# pwr.net
KiCad netlist of a schematic drawn in Altium Designer
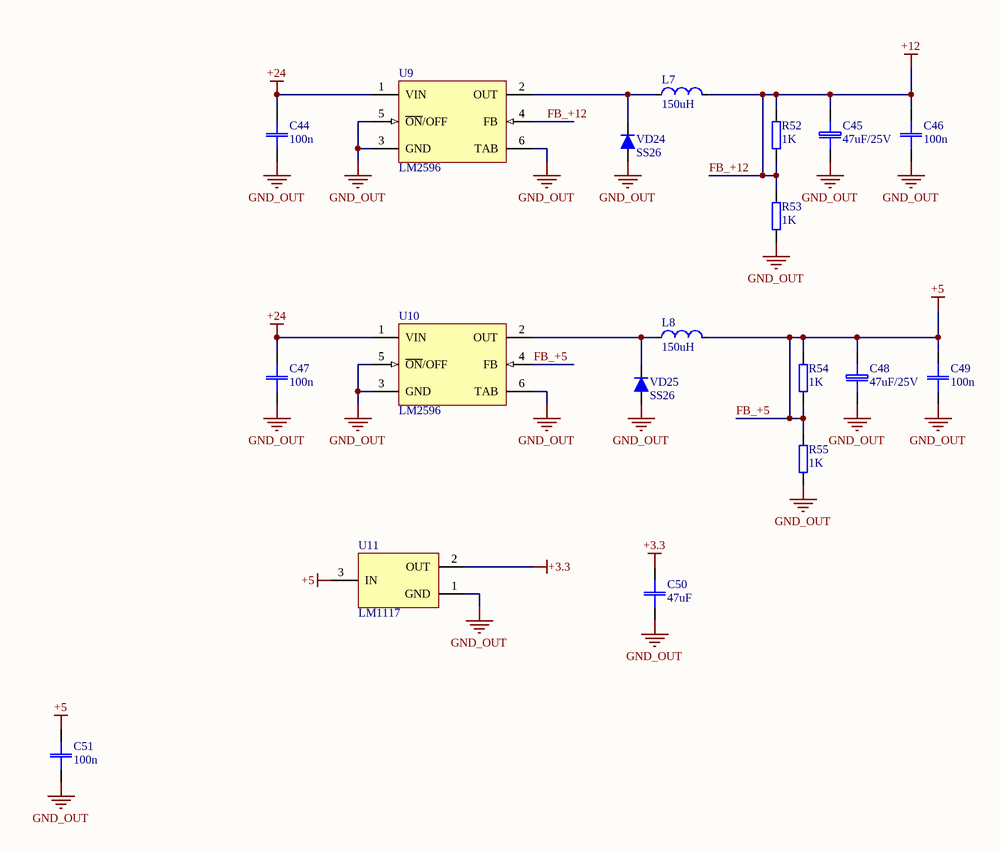
[diagram p0: pwr.SchDoc]

(export (version "E")
  (design (tool "Eeschema 10.0.6"))
  (components
    (comp (ref "C44") (value "100n") (footprint "CAP: 1206") (libsource (lib "PASSIVE") (part "C_SMD")))
    (comp (ref "C45")
      (value "47uF/25V")
      (footprint "CAP: TANTAL-C")
      (libsource (lib "PASSIVE") (part "C_TANTAL"))
    )
    (comp (ref "C46") (value "100n") (footprint "CAP: 0805") (libsource (lib "PASSIVE") (part "C_SMD")))
    (comp (ref "C47") (value "100n") (footprint "CAP: 1206") (libsource (lib "PASSIVE") (part "C_SMD")))
    (comp (ref "C48")
      (value "47uF/25V")
      (footprint "CAP: TANTAL-C")
      (libsource (lib "PASSIVE") (part "C_TANTAL"))
    )
    (comp (ref "C49") (value "100n") (footprint "CAP: 0805") (libsource (lib "PASSIVE") (part "C_SMD")))
    (comp (ref "C50") (value "47uF") (footprint "CAP: 0805") (libsource (lib "PASSIVE") (part "C_SMD")))
    (comp (ref "C51") (value "100n") (footprint "CAP: 0805") (libsource (lib "PASSIVE") (part "C_SMD")))
    (comp (ref "L7") (value "150uH") (footprint "IND: SRP1265A") (libsource (lib "PASSIVE") (part "L_SMD")))
    (comp (ref "L8") (value "150uH") (footprint "IND: SRP1265A") (libsource (lib "PASSIVE") (part "L_SMD")))
    (comp (ref "R52") (value "1K") (footprint "RES: 0603") (libsource (lib "PASSIVE") (part "R_SMD")))
    (comp (ref "R53") (value "1K") (footprint "RES: 0603") (libsource (lib "PASSIVE") (part "R_SMD")))
    (comp (ref "R54") (value "1K") (footprint "RES: 0603") (libsource (lib "PASSIVE") (part "R_SMD")))
    (comp (ref "R55") (value "1K") (footprint "RES: 0603") (libsource (lib "PASSIVE") (part "R_SMD")))
    (comp (ref "U9") (value "LM2596") (footprint "POW: D2PAK-5") (libsource (lib "POWER") (part "LM2596")))
    (comp (ref "U10") (value "LM2596") (footprint "POW: D2PAK-5") (libsource (lib "POWER") (part "LM2596")))
    (comp (ref "U11") (value "LM1117") (footprint "SOT223") (libsource (lib "POWER") (part "LM1117")))
    (comp (ref "VD24") (value "SS26") (footprint "DIODE: SMA") (libsource (lib "DIODES") (part "DIODE_SMD")))
    (comp (ref "VD25") (value "SS26") (footprint "DIODE: SMA") (libsource (lib "DIODES") (part "DIODE_SMD")))
  )
  (nets
    (net (code "1") (name "+3.3") (class "Default")
      (node (ref "C50") (pin "2") (pinfunction "2_2") (pintype "passive"))
      (node (ref "U11") (pin "2") (pinfunction "OUT_2") (pintype "power_in"))
    )
    (net (code "2") (name "+5") (class "Default")
      (node (ref "C48") (pin "1") (pinfunction "+_1") (pintype "passive"))
      (node (ref "C49") (pin "2") (pinfunction "2_2") (pintype "passive"))
      (node (ref "C51") (pin "2") (pinfunction "2_2") (pintype "passive"))
      (node (ref "L8") (pin "2") (pinfunction "2_2") (pintype "passive"))
      (node (ref "R54") (pin "1") (pinfunction "1_1") (pintype "passive"))
      (node (ref "R54") (pin "2") (pinfunction "2_2") (pintype "passive"))
      (node (ref "R55") (pin "1") (pinfunction "1_1") (pintype "passive"))
      (node (ref "U10") (pin "4") (pinfunction "FB_4") (pintype "input"))
      (node (ref "U11") (pin "3") (pinfunction "IN_3") (pintype "power_in"))
    )
    (net (code "3") (name "+12") (class "Default")
      (node (ref "C45") (pin "1") (pinfunction "+_1") (pintype "passive"))
      (node (ref "C46") (pin "2") (pinfunction "2_2") (pintype "passive"))
      (node (ref "L7") (pin "2") (pinfunction "2_2") (pintype "passive"))
      (node (ref "R52") (pin "1") (pinfunction "1_1") (pintype "passive"))
      (node (ref "R52") (pin "2") (pinfunction "2_2") (pintype "passive"))
      (node (ref "R53") (pin "1") (pinfunction "1_1") (pintype "passive"))
      (node (ref "U9") (pin "4") (pinfunction "FB_4") (pintype "input"))
    )
    (net (code "4") (name "+24") (class "Default")
      (node (ref "C44") (pin "2") (pinfunction "2_2") (pintype "passive"))
      (node (ref "C47") (pin "2") (pinfunction "2_2") (pintype "passive"))
      (node (ref "U10") (pin "1") (pinfunction "VIN_1") (pintype "power_in"))
      (node (ref "U9") (pin "1") (pinfunction "VIN_1") (pintype "power_in"))
    )
    (net (code "5") (name "GND_OUT") (class "Default")
      (node (ref "C44") (pin "1") (pinfunction "1_1") (pintype "passive"))
      (node (ref "C45") (pin "2") (pinfunction "-_2") (pintype "passive"))
      (node (ref "C46") (pin "1") (pinfunction "1_1") (pintype "passive"))
      (node (ref "C47") (pin "1") (pinfunction "1_1") (pintype "passive"))
      (node (ref "C48") (pin "2") (pinfunction "-_2") (pintype "passive"))
      (node (ref "C49") (pin "1") (pinfunction "1_1") (pintype "passive"))
      (node (ref "C50") (pin "1") (pinfunction "1_1") (pintype "passive"))
      (node (ref "C51") (pin "1") (pinfunction "1_1") (pintype "passive"))
      (node (ref "R53") (pin "2") (pinfunction "2_2") (pintype "passive"))
      (node (ref "R55") (pin "2") (pinfunction "2_2") (pintype "passive"))
      (node (ref "U10") (pin "3") (pinfunction "GND_3") (pintype "power_in"))
      (node (ref "U10") (pin "5") (pinfunction "~{ON}/OFF_5") (pintype "input"))
      (node (ref "U10") (pin "6") (pinfunction "TAB_6") (pintype "power_in"))
      (node (ref "U11") (pin "1") (pinfunction "GND_1") (pintype "power_in"))
      (node (ref "U9") (pin "3") (pinfunction "GND_3") (pintype "power_in"))
      (node (ref "U9") (pin "5") (pinfunction "~{ON}/OFF_5") (pintype "input"))
      (node (ref "U9") (pin "6") (pinfunction "TAB_6") (pintype "power_in"))
      (node (ref "VD24") (pin "1") (pinfunction "A_1") (pintype "passive"))
      (node (ref "VD25") (pin "1") (pinfunction "A_1") (pintype "passive"))
    )
    (net (code "6") (name "Net-(U9-OUT)") (class "Default")
      (node (ref "L7") (pin "1") (pinfunction "1_1") (pintype "passive"))
      (node (ref "U9") (pin "2") (pinfunction "OUT_2") (pintype "power_in"))
      (node (ref "VD24") (pin "2") (pinfunction "C_2") (pintype "passive"))
    )
    (net (code "7") (name "Net-(U10-OUT)") (class "Default")
      (node (ref "L8") (pin "1") (pinfunction "1_1") (pintype "passive"))
      (node (ref "U10") (pin "2") (pinfunction "OUT_2") (pintype "power_in"))
      (node (ref "VD25") (pin "2") (pinfunction "C_2") (pintype "passive"))
    )
  )
)
